# Capacitive_touch.net
KiCad netlist of a schematic drawn in Altium Designer
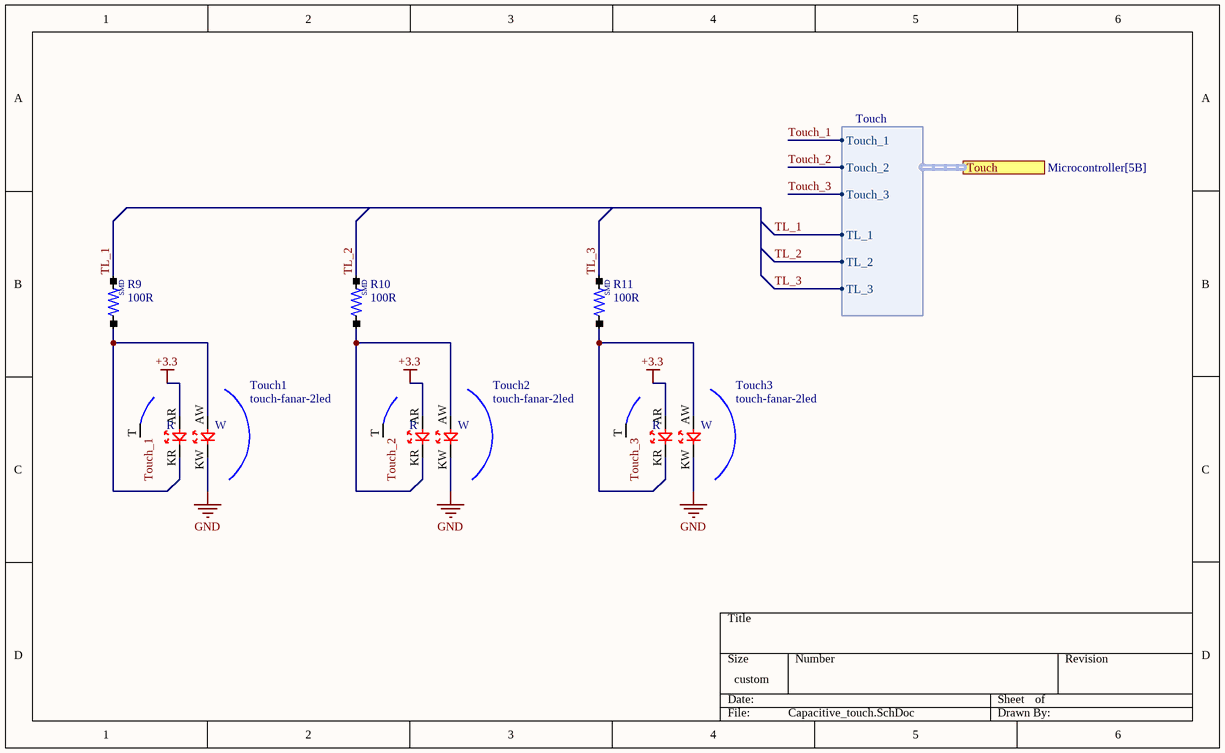
[diagram p0: Capacitive_touch.SchDoc]

(export (version "E")
  (design (tool "Eeschema 10.0.6"))
  (components
    (comp (ref "R9") (value "100R") (footprint "RES/0603") (libsource (lib "kave-eng-pro") (part "RES/SMD")))
    (comp (ref "R10") (value "100R") (footprint "RES/0603") (libsource (lib "kave-eng-pro") (part "RES/SMD")))
    (comp (ref "R11") (value "100R") (footprint "RES/0603") (libsource (lib "kave-eng-pro") (part "RES/SMD")))
    (comp (ref "Touch1")
      (value "touch-fanar-2led")
      (footprint "fanar-touch-2led")
      (libsource (lib "kave-eng-pro") (part "touch-fanar-2led"))
    )
    (comp (ref "Touch2")
      (value "touch-fanar-2led")
      (footprint "fanar-touch-2led")
      (libsource (lib "kave-eng-pro") (part "touch-fanar-2led"))
    )
    (comp (ref "Touch3")
      (value "touch-fanar-2led")
      (footprint "fanar-touch-2led")
      (libsource (lib "kave-eng-pro") (part "touch-fanar-2led"))
    )
  )
  (nets
    (net (code "2") (name "+3.3") (class "Default")
      (node (ref "Touch1") (pin "AR") (pintype "passive"))
      (node (ref "Touch2") (pin "AR") (pintype "passive"))
      (node (ref "Touch3") (pin "AR") (pintype "passive"))
    )
    (net (code "3") (name "/TL_1") (class "Default")
      (node (ref "R9") (pin "2") (pinfunction "2_2") (pintype "passive"))
    )
    (net (code "4") (name "/TL_2") (class "Default")
      (node (ref "R10") (pin "2") (pinfunction "2_2") (pintype "passive"))
    )
    (net (code "5") (name "/TL_3") (class "Default")
      (node (ref "R11") (pin "2") (pinfunction "2_2") (pintype "passive"))
    )
    (net (code "6") (name "/Touch_1") (class "Default") (node (ref "Touch1") (pin "T") (pintype "passive")))
    (net (code "7") (name "/Touch_2") (class "Default") (node (ref "Touch2") (pin "T") (pintype "passive")))
    (net (code "8") (name "/Touch_3") (class "Default") (node (ref "Touch3") (pin "T") (pintype "passive")))
    (net (code "10") (name "GND") (class "Default")
      (node (ref "Touch1") (pin "KW") (pintype "passive"))
      (node (ref "Touch2") (pin "KW") (pintype "passive"))
      (node (ref "Touch3") (pin "KW") (pintype "passive"))
    )
    (net (code "11") (name "Net-(R9-Pad1)") (class "Default")
      (node (ref "R9") (pin "1") (pinfunction "1_1") (pintype "passive"))
      (node (ref "Touch1") (pin "AW") (pintype "passive"))
      (node (ref "Touch1") (pin "KR") (pintype "passive"))
    )
    (net (code "12") (name "Net-(R10-Pad1)") (class "Default")
      (node (ref "R10") (pin "1") (pinfunction "1_1") (pintype "passive"))
      (node (ref "Touch2") (pin "AW") (pintype "passive"))
      (node (ref "Touch2") (pin "KR") (pintype "passive"))
    )
    (net (code "13") (name "Net-(R11-Pad1)") (class "Default")
      (node (ref "R11") (pin "1") (pinfunction "1_1") (pintype "passive"))
      (node (ref "Touch3") (pin "AW") (pintype "passive"))
      (node (ref "Touch3") (pin "KR") (pintype "passive"))
    )
  )
)
